# Tag_PCB_V1.net
KiCad netlist of a schematic drawn in EAGLE
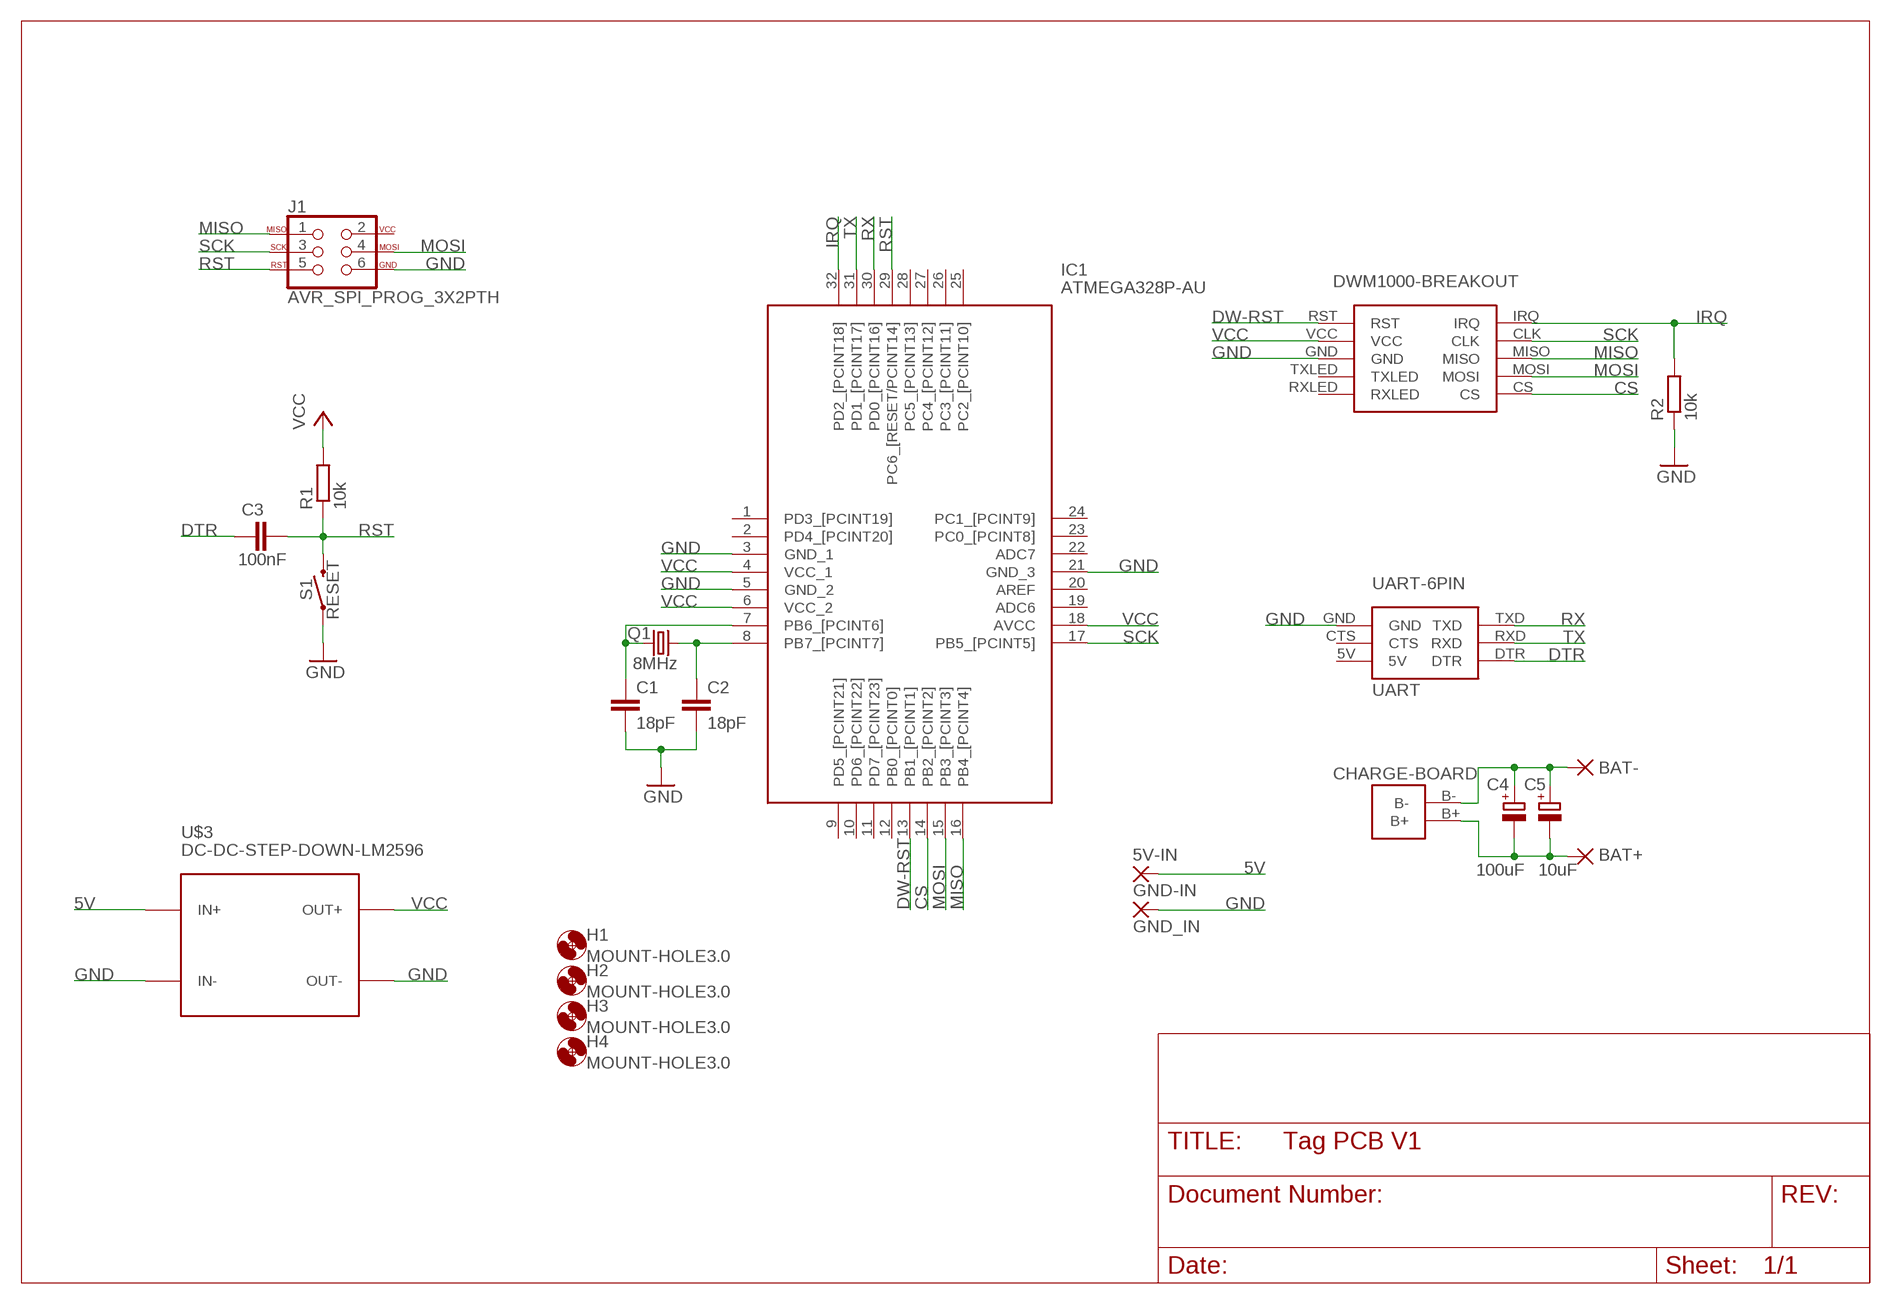
[diagram p0: schematic, sheet 1]

(export (version "E")
  (design (tool "Eeschema 10.0.6"))
  (components
    (comp (ref "5V-IN")
      (value "2,15/1,0")
      (footprint "eagle-import:2,15_1,0")
      (libsource (lib "eagle-import") (part "2,15/1,0"))
    )
    (comp (ref "BAT+")
      (value "2,15/1,0")
      (footprint "eagle-import:2,15_1,0")
      (libsource (lib "eagle-import") (part "2,15/1,0"))
    )
    (comp (ref "BAT-")
      (value "2,15/1,0")
      (footprint "eagle-import:2,15_1,0")
      (libsource (lib "eagle-import") (part "2,15/1,0"))
    )
    (comp (ref "C1")
      (value "18pF")
      (footprint "eagle-import:C0805")
      (libsource (lib "eagle-import") (part "C-EUC0805"))
    )
    (comp (ref "C2")
      (value "18pF")
      (footprint "eagle-import:C0805")
      (libsource (lib "eagle-import") (part "C-EUC0805"))
    )
    (comp (ref "C3")
      (value "100nF")
      (footprint "eagle-import:C0805")
      (libsource (lib "eagle-import") (part "C-EUC0805"))
    )
    (comp (ref "C4")
      (value "100uF")
      (footprint "eagle-import:E3,5-8")
      (libsource (lib "eagle-import") (part "CPOL-EUE3.5-8"))
    )
    (comp (ref "C5")
      (value "10uF")
      (footprint "eagle-import:E2,5-7")
      (libsource (lib "eagle-import") (part "CPOL-EUE2.5-7"))
    )
    (comp (ref "GND-IN")
      (value "GND_IN")
      (footprint "eagle-import:2,15_1,0")
      (libsource (lib "eagle-import") (part "2,15/1,0"))
    )
    (comp (ref "H1")
      (value "MOUNT-HOLE3.0")
      (footprint "eagle-import:3,0")
      (libsource (lib "eagle-import") (part "MOUNT-HOLE3.0"))
    )
    (comp (ref "H2")
      (value "MOUNT-HOLE3.0")
      (footprint "eagle-import:3,0")
      (libsource (lib "eagle-import") (part "MOUNT-HOLE3.0"))
    )
    (comp (ref "H3")
      (value "MOUNT-HOLE3.0")
      (footprint "eagle-import:3,0")
      (libsource (lib "eagle-import") (part "MOUNT-HOLE3.0"))
    )
    (comp (ref "H4")
      (value "MOUNT-HOLE3.0")
      (footprint "eagle-import:3,0")
      (libsource (lib "eagle-import") (part "MOUNT-HOLE3.0"))
    )
    (comp (ref "IC1")
      (value "ATMEGA328P-AU")
      (footprint "eagle-import:QFP80P900X900X120-32N")
      (fields (field (name "RS_PART_NUMBER") "1310271"))
      (libsource (lib "eagle-import") (part "ATMEGA328P-AU"))
    )
    (comp (ref "J1")
      (value "AVR_SPI_PROG_3X2PTH")
      (footprint "eagle-import:2X3")
      (libsource (lib "eagle-import") (part "AVR_SPI_PROG_3X2PTH"))
    )
    (comp (ref "Q1")
      (value "8MHz")
      (footprint "eagle-import:HC49UP")
      (libsource (lib "eagle-import") (part "CRYSTALHC49UP"))
    )
    (comp (ref "R1")
      (value "10k")
      (footprint "eagle-import:R0805")
      (libsource (lib "eagle-import") (part "R-EU_R0805"))
    )
    (comp (ref "R2")
      (value "10k")
      (footprint "eagle-import:R0805")
      (libsource (lib "eagle-import") (part "R-EU_R0805"))
    )
    (comp (ref "S1")
      (value "RESET")
      (footprint "eagle-import:TACTILE_SWITCH_PTH_6.0MM")
      (libsource (lib "eagle-import") (part "MOMENTARY-SWITCH-SPST-PTH-6.0MM"))
    )
    (comp (ref "U$1")
      (value "DWM1000-BREAKOUT")
      (footprint "eagle-import:DWM1000-BREAKOUT")
      (libsource (lib "eagle-import") (part "DWM1000-BREAKOUT"))
    )
    (comp (ref "U$2")
      (value "UART-6PIN")
      (footprint "eagle-import:UART-6PIN")
      (libsource (lib "eagle-import") (part "UART-6PIN"))
    )
    (comp (ref "U$3")
      (value "DC-DC-STEP-DOWN-LM2596")
      (footprint "eagle-import:DC-DC-STEP-DOWN-LM2596")
      (libsource (lib "eagle-import") (part "DC-DC-STEP-DOWN-LM2596"))
    )
    (comp (ref "U$4")
      (value "18650-CHARGE-5V-OUT")
      (footprint "eagle-import:18650-CHARGE-5V-OUT")
      (libsource (lib "eagle-import") (part "18650-CHARGE-5V-OUT"))
    )
  )
  (nets
    (net (code "1") (name "/5V") (class "Default")
      (node (ref "5V-IN") (pin "1") (pinfunction "P_1") (pintype "passive"))
      (node (ref "U$3") (pin "IN+") (pinfunction "IN+_IN+") (pintype "bidirectional"))
    )
    (net (code "2") (name "/CS") (class "Default")
      (node (ref "IC1") (pin "14") (pinfunction "PB2_[PCINT2]_14") (pintype "bidirectional"))
      (node (ref "U$1") (pin "CS") (pinfunction "CS_CS") (pintype "bidirectional"))
    )
    (net (code "3") (name "/DTR") (class "Default")
      (node (ref "C3") (pin "1") (pinfunction "1_1") (pintype "passive"))
      (node (ref "U$2") (pin "DTR") (pinfunction "DTR_DTR") (pintype "bidirectional"))
    )
    (net (code "4") (name "/DW-RST") (class "Default")
      (node (ref "IC1") (pin "13") (pinfunction "PB1_[PCINT1]_13") (pintype "bidirectional"))
      (node (ref "U$1") (pin "RST") (pinfunction "RST_RST") (pintype "bidirectional"))
    )
    (net (code "5") (name "/IRQ") (class "Default")
      (node (ref "IC1") (pin "32") (pinfunction "PD2_[PCINT18]_32") (pintype "bidirectional"))
      (node (ref "R2") (pin "2") (pinfunction "2_2") (pintype "passive"))
      (node (ref "U$1") (pin "IRQ") (pinfunction "IRQ_IRQ") (pintype "bidirectional"))
    )
    (net (code "6") (name "/MISO") (class "Default")
      (node (ref "IC1") (pin "16") (pinfunction "PB4_[PCINT4]_16") (pintype "bidirectional"))
      (node (ref "J1") (pin "1") (pinfunction "1_1") (pintype "passive"))
      (node (ref "U$1") (pin "MISO") (pinfunction "MISO_MISO") (pintype "bidirectional"))
    )
    (net (code "7") (name "/MOSI") (class "Default")
      (node (ref "IC1") (pin "15") (pinfunction "PB3_[PCINT3]_15") (pintype "bidirectional"))
      (node (ref "J1") (pin "4") (pinfunction "4_4") (pintype "passive"))
      (node (ref "U$1") (pin "MOSI") (pinfunction "MOSI_MOSI") (pintype "bidirectional"))
    )
    (net (code "8") (name "/RST") (class "Default")
      (node (ref "C3") (pin "2") (pinfunction "2_2") (pintype "passive"))
      (node (ref "IC1") (pin "29") (pinfunction "PC6_[RESET/PCINT14]_29") (pintype "bidirectional"))
      (node (ref "J1") (pin "5") (pinfunction "5_5") (pintype "passive"))
      (node (ref "R1") (pin "1") (pinfunction "1_1") (pintype "passive"))
      (node (ref "S1") (pin "3") (pinfunction "2_3") (pintype "passive"))
    )
    (net (code "9") (name "/RX") (class "Default")
      (node (ref "IC1") (pin "30") (pinfunction "PD0_[PCINT16]_30") (pintype "bidirectional"))
      (node (ref "U$2") (pin "TXD") (pinfunction "TXD_TXD") (pintype "bidirectional"))
    )
    (net (code "10") (name "/SCK") (class "Default")
      (node (ref "IC1") (pin "17") (pinfunction "PB5_[PCINT5]_17") (pintype "bidirectional"))
      (node (ref "J1") (pin "3") (pinfunction "3_3") (pintype "passive"))
      (node (ref "U$1") (pin "CLK") (pinfunction "CLK_CLK") (pintype "bidirectional"))
    )
    (net (code "11") (name "/TX") (class "Default")
      (node (ref "IC1") (pin "31") (pinfunction "PD1_[PCINT17]_31") (pintype "bidirectional"))
      (node (ref "U$2") (pin "RXD") (pinfunction "RXD_RXD") (pintype "bidirectional"))
    )
    (net (code "12") (name "GND") (class "Default")
      (node (ref "C1") (pin "2") (pinfunction "2_2") (pintype "passive"))
      (node (ref "C2") (pin "2") (pinfunction "2_2") (pintype "passive"))
      (node (ref "GND-IN") (pin "1") (pinfunction "P_1") (pintype "passive"))
      (node (ref "IC1") (pin "21") (pinfunction "GND_3_21") (pintype "power_in"))
      (node (ref "IC1") (pin "3") (pinfunction "GND_1_3") (pintype "power_in"))
      (node (ref "IC1") (pin "5") (pinfunction "GND_2_5") (pintype "power_in"))
      (node (ref "J1") (pin "6") (pinfunction "6_6") (pintype "passive"))
      (node (ref "R2") (pin "1") (pinfunction "1_1") (pintype "passive"))
      (node (ref "S1") (pin "1") (pinfunction "1_1") (pintype "passive"))
      (node (ref "U$1") (pin "GND") (pinfunction "GND_GND") (pintype "bidirectional"))
      (node (ref "U$2") (pin "GND") (pinfunction "GND_GND") (pintype "bidirectional"))
      (node (ref "U$3") (pin "IN-") (pinfunction "IN-_IN-") (pintype "bidirectional"))
      (node (ref "U$3") (pin "OUT-") (pinfunction "OUT-_OUT-") (pintype "bidirectional"))
    )
    (net (code "13") (name "Net-(BAT+-P)") (class "Default")
      (node (ref "BAT+") (pin "1") (pinfunction "P_1") (pintype "passive"))
      (node (ref "C4") (pin "-") (pinfunction "-_-") (pintype "passive"))
      (node (ref "C5") (pin "-") (pinfunction "-_-") (pintype "passive"))
      (node (ref "U$4") (pin "B+") (pinfunction "B+_B+") (pintype "bidirectional"))
    )
    (net (code "14") (name "Net-(BAT--P)") (class "Default")
      (node (ref "BAT-") (pin "1") (pinfunction "P_1") (pintype "passive"))
      (node (ref "C4") (pin "+") (pinfunction "+_+") (pintype "passive"))
      (node (ref "C5") (pin "+") (pinfunction "+_+") (pintype "passive"))
      (node (ref "U$4") (pin "B-") (pinfunction "B-_B-") (pintype "bidirectional"))
    )
    (net (code "15") (name "Net-(IC1-PB6_[PCINT6])") (class "Default")
      (node (ref "C1") (pin "1") (pinfunction "1_1") (pintype "passive"))
      (node (ref "IC1") (pin "7") (pinfunction "PB6_[PCINT6]_7") (pintype "bidirectional"))
      (node (ref "Q1") (pin "1") (pinfunction "1_1") (pintype "passive"))
    )
    (net (code "16") (name "Net-(IC1-PB7_[PCINT7])") (class "Default")
      (node (ref "C2") (pin "1") (pinfunction "1_1") (pintype "passive"))
      (node (ref "IC1") (pin "8") (pinfunction "PB7_[PCINT7]_8") (pintype "bidirectional"))
      (node (ref "Q1") (pin "2") (pinfunction "2_2") (pintype "passive"))
    )
    (net (code "17") (name "VCC") (class "Default")
      (node (ref "IC1") (pin "18") (pinfunction "AVCC_18") (pintype "power_in"))
      (node (ref "IC1") (pin "4") (pinfunction "VCC_1_4") (pintype "power_in"))
      (node (ref "IC1") (pin "6") (pinfunction "VCC_2_6") (pintype "power_in"))
      (node (ref "R1") (pin "2") (pinfunction "2_2") (pintype "passive"))
      (node (ref "U$1") (pin "VCC") (pinfunction "VCC_VCC") (pintype "bidirectional"))
      (node (ref "U$3") (pin "OUT+") (pinfunction "OUT+_OUT+") (pintype "bidirectional"))
    )
    (net (code "18") (name "unconnected-(IC1-ADC6-Pad19)") (class "Default")
      (node (ref "IC1") (pin "19") (pinfunction "ADC6_19") (pintype "bidirectional"))
    )
    (net (code "19") (name "unconnected-(IC1-ADC7-Pad22)") (class "Default")
      (node (ref "IC1") (pin "22") (pinfunction "ADC7_22") (pintype "bidirectional"))
    )
    (net (code "20") (name "unconnected-(IC1-AREF-Pad20)") (class "Default")
      (node (ref "IC1") (pin "20") (pinfunction "AREF_20") (pintype "bidirectional"))
    )
    (net (code "21") (name "unconnected-(IC1-PB0_[PCINT0]-Pad12)") (class "Default")
      (node (ref "IC1") (pin "12") (pinfunction "PB0_[PCINT0]_12") (pintype "bidirectional"))
    )
    (net (code "22") (name "unconnected-(IC1-PC0_[PCINT8]-Pad23)") (class "Default")
      (node (ref "IC1") (pin "23") (pinfunction "PC0_[PCINT8]_23") (pintype "bidirectional"))
    )
    (net (code "23") (name "unconnected-(IC1-PC1_[PCINT9]-Pad24)") (class "Default")
      (node (ref "IC1") (pin "24") (pinfunction "PC1_[PCINT9]_24") (pintype "bidirectional"))
    )
    (net (code "24") (name "unconnected-(IC1-PC2_[PCINT10]-Pad25)") (class "Default")
      (node (ref "IC1") (pin "25") (pinfunction "PC2_[PCINT10]_25") (pintype "bidirectional"))
    )
    (net (code "25") (name "unconnected-(IC1-PC3_[PCINT11]-Pad26)") (class "Default")
      (node (ref "IC1") (pin "26") (pinfunction "PC3_[PCINT11]_26") (pintype "bidirectional"))
    )
    (net (code "26") (name "unconnected-(IC1-PC4_[PCINT12]-Pad27)") (class "Default")
      (node (ref "IC1") (pin "27") (pinfunction "PC4_[PCINT12]_27") (pintype "bidirectional"))
    )
    (net (code "27") (name "unconnected-(IC1-PC5_[PCINT13]-Pad28)") (class "Default")
      (node (ref "IC1") (pin "28") (pinfunction "PC5_[PCINT13]_28") (pintype "bidirectional"))
    )
    (net (code "28") (name "unconnected-(IC1-PD3_[PCINT19]-Pad1)") (class "Default")
      (node (ref "IC1") (pin "1") (pinfunction "PD3_[PCINT19]_1") (pintype "bidirectional"))
    )
    (net (code "29") (name "unconnected-(IC1-PD4_[PCINT20]-Pad2)") (class "Default")
      (node (ref "IC1") (pin "2") (pinfunction "PD4_[PCINT20]_2") (pintype "bidirectional"))
    )
    (net (code "30") (name "unconnected-(IC1-PD5_[PCINT21]-Pad9)") (class "Default")
      (node (ref "IC1") (pin "9") (pinfunction "PD5_[PCINT21]_9") (pintype "bidirectional"))
    )
    (net (code "31") (name "unconnected-(IC1-PD6_[PCINT22]-Pad10)") (class "Default")
      (node (ref "IC1") (pin "10") (pinfunction "PD6_[PCINT22]_10") (pintype "bidirectional"))
    )
    (net (code "32") (name "unconnected-(IC1-PD7_[PCINT23]-Pad11)") (class "Default")
      (node (ref "IC1") (pin "11") (pinfunction "PD7_[PCINT23]_11") (pintype "bidirectional"))
    )
    (net (code "33") (name "unconnected-(J1-Pad2)") (class "Default")
      (node (ref "J1") (pin "2") (pinfunction "2_2") (pintype "passive"))
    )
    (net (code "34") (name "unconnected-(U$1-PadRXLED)") (class "Default")
      (node (ref "U$1") (pin "RXLED") (pinfunction "RXLED_RXLED") (pintype "bidirectional"))
    )
    (net (code "35") (name "unconnected-(U$1-PadTXLED)") (class "Default")
      (node (ref "U$1") (pin "TXLED") (pinfunction "TXLED_TXLED") (pintype "bidirectional"))
    )
    (net (code "36") (name "unconnected-(U$2-Pad5V)") (class "Default")
      (node (ref "U$2") (pin "5V") (pinfunction "5V_5V") (pintype "bidirectional"))
    )
    (net (code "37") (name "unconnected-(U$2-PadCTS)") (class "Default")
      (node (ref "U$2") (pin "CTS") (pinfunction "CTS_CTS") (pintype "bidirectional"))
    )
  )
)
